# Open_Reactor_Control_System_-_Power_Supp.net
KiCad netlist of a schematic drawn in Altium Designer
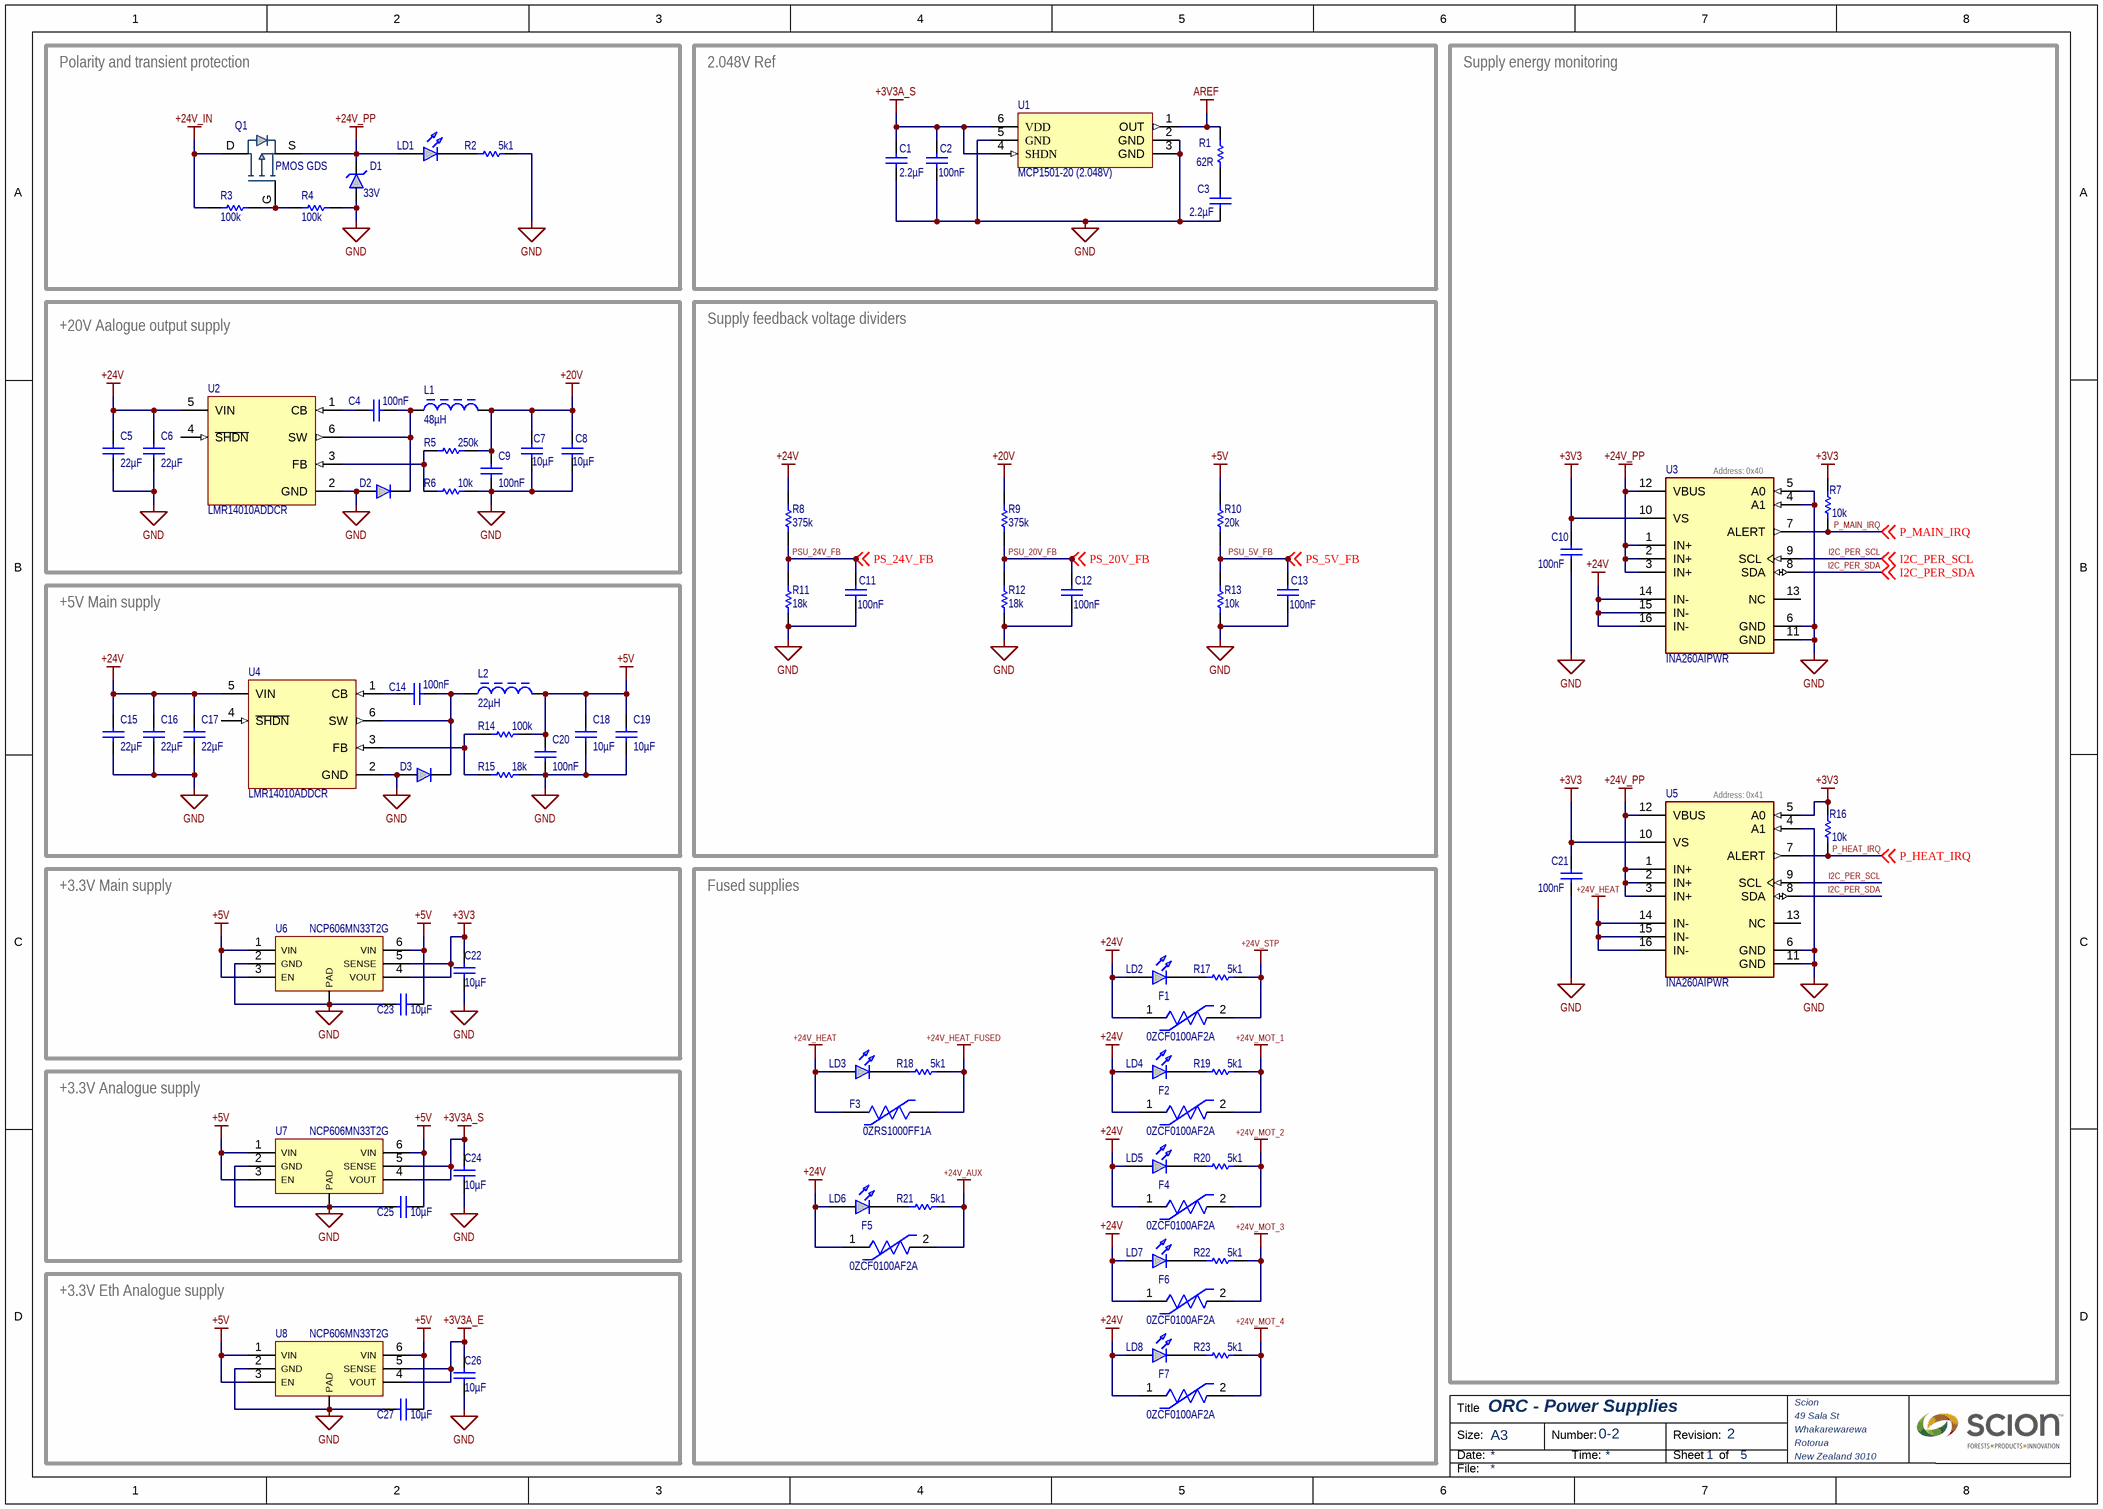
[diagram p0: Open Reactor Control System - Power Supplies.SchDoc]

(export (version "E")
  (design (tool "Eeschema 10.0.6"))
  (components
    (comp (ref "C1")
      (value "2.2µF")
      (footprint "0603_CAP")
      (description "SMD Capacitor")
      (fields (field (name "Comment") "Capacitor"))
      (libsource (lib "Scion Research") (part "CMP-019-00005-2"))
    )
    (comp (ref "C2")
      (value "100nF")
      (footprint "0603_CAP")
      (description "SMD Capacitor")
      (fields (field (name "Comment") "Capacitor"))
      (libsource (lib "Scion Research") (part "CMP-019-00005-2"))
    )
    (comp (ref "C3")
      (value "2.2µF")
      (footprint "0603_CAP")
      (description "SMD Capacitor")
      (fields (field (name "Comment") "Capacitor"))
      (libsource (lib "Scion Research") (part "CMP-019-00005-2"))
    )
    (comp (ref "C4")
      (value "100nF")
      (footprint "0603_CAP")
      (description "SMD Capacitor")
      (fields (field (name "Comment") "Capacitor"))
      (libsource (lib "Scion Research") (part "CMP-019-00005-2"))
    )
    (comp (ref "C5")
      (value "22µF")
      (footprint "1206_CAP")
      (description "SMD Capacitor")
      (fields (field (name "Comment") "Capacitor"))
      (libsource (lib "Scion Research") (part "CMP-019-00005-2"))
    )
    (comp (ref "C6")
      (value "22µF")
      (footprint "1206_CAP")
      (description "SMD Capacitor")
      (fields (field (name "Comment") "Capacitor"))
      (libsource (lib "Scion Research") (part "CMP-019-00005-2"))
    )
    (comp (ref "C7")
      (value "10µF")
      (footprint "1206_CAP")
      (description "SMD Capacitor")
      (fields (field (name "Comment") "Capacitor"))
      (libsource (lib "Scion Research") (part "CMP-019-00005-2"))
    )
    (comp (ref "C8")
      (value "10µF")
      (footprint "1206_CAP")
      (description "SMD Capacitor")
      (fields (field (name "Comment") "Capacitor"))
      (libsource (lib "Scion Research") (part "CMP-019-00005-2"))
    )
    (comp (ref "C9")
      (value "100nF")
      (footprint "0603_CAP")
      (description "SMD Capacitor")
      (fields (field (name "Comment") "Capacitor"))
      (libsource (lib "Scion Research") (part "CMP-019-00005-2"))
    )
    (comp (ref "C10")
      (value "100nF")
      (footprint "0603_CAP")
      (description "SMD Capacitor")
      (fields (field (name "Comment") "Capacitor"))
      (libsource (lib "Scion Research") (part "CMP-019-00005-2"))
    )
    (comp (ref "C11")
      (value "100nF")
      (footprint "0603_CAP")
      (description "SMD Capacitor")
      (fields (field (name "Comment") "Capacitor"))
      (libsource (lib "Scion Research") (part "CMP-019-00005-2"))
    )
    (comp (ref "C12")
      (value "100nF")
      (footprint "0603_CAP")
      (description "SMD Capacitor")
      (fields (field (name "Comment") "Capacitor"))
      (libsource (lib "Scion Research") (part "CMP-019-00005-2"))
    )
    (comp (ref "C13")
      (value "100nF")
      (footprint "0603_CAP")
      (description "SMD Capacitor")
      (fields (field (name "Comment") "Capacitor"))
      (libsource (lib "Scion Research") (part "CMP-019-00005-2"))
    )
    (comp (ref "C14")
      (value "100nF")
      (footprint "0603_CAP")
      (description "SMD Capacitor")
      (fields (field (name "Comment") "Capacitor"))
      (libsource (lib "Scion Research") (part "CMP-019-00005-2"))
    )
    (comp (ref "C15")
      (value "22µF")
      (footprint "1206_CAP")
      (description "SMD Capacitor")
      (fields (field (name "Comment") "Capacitor"))
      (libsource (lib "Scion Research") (part "CMP-019-00005-2"))
    )
    (comp (ref "C16")
      (value "22µF")
      (footprint "1206_CAP")
      (description "SMD Capacitor")
      (fields (field (name "Comment") "Capacitor"))
      (libsource (lib "Scion Research") (part "CMP-019-00005-2"))
    )
    (comp (ref "C17")
      (value "22µF")
      (footprint "1206_CAP")
      (description "SMD Capacitor")
      (fields (field (name "Comment") "Capacitor"))
      (libsource (lib "Scion Research") (part "CMP-019-00005-2"))
    )
    (comp (ref "C18")
      (value "10µF")
      (footprint "0603_CAP")
      (description "SMD Capacitor")
      (fields (field (name "Comment") "Capacitor"))
      (libsource (lib "Scion Research") (part "CMP-019-00005-2"))
    )
    (comp (ref "C19")
      (value "10µF")
      (footprint "0603_CAP")
      (description "SMD Capacitor")
      (fields (field (name "Comment") "Capacitor"))
      (libsource (lib "Scion Research") (part "CMP-019-00005-2"))
    )
    (comp (ref "C20")
      (value "100nF")
      (footprint "0603_CAP")
      (description "SMD Capacitor")
      (fields (field (name "Comment") "Capacitor"))
      (libsource (lib "Scion Research") (part "CMP-019-00005-2"))
    )
    (comp (ref "C21")
      (value "100nF")
      (footprint "0603_CAP")
      (description "SMD Capacitor")
      (fields (field (name "Comment") "Capacitor"))
      (libsource (lib "Scion Research") (part "CMP-019-00005-2"))
    )
    (comp (ref "C22")
      (value "10µF")
      (footprint "0603_CAP")
      (description "SMD Capacitor")
      (fields (field (name "Comment") "Capacitor"))
      (libsource (lib "Scion Research") (part "CMP-019-00005-2"))
    )
    (comp (ref "C23")
      (value "10µF")
      (footprint "0603_CAP")
      (description "SMD Capacitor")
      (fields (field (name "Comment") "Capacitor"))
      (libsource (lib "Scion Research") (part "CMP-019-00005-2"))
    )
    (comp (ref "C24")
      (value "10µF")
      (footprint "0603_CAP")
      (description "SMD Capacitor")
      (fields (field (name "Comment") "Capacitor"))
      (libsource (lib "Scion Research") (part "CMP-019-00005-2"))
    )
    (comp (ref "C25")
      (value "10µF")
      (footprint "0603_CAP")
      (description "SMD Capacitor")
      (fields (field (name "Comment") "Capacitor"))
      (libsource (lib "Scion Research") (part "CMP-019-00005-2"))
    )
    (comp (ref "C26")
      (value "10µF")
      (footprint "0603_CAP")
      (description "SMD Capacitor")
      (fields (field (name "Comment") "Capacitor"))
      (libsource (lib "Scion Research") (part "CMP-019-00005-2"))
    )
    (comp (ref "C27")
      (value "10µF")
      (footprint "0603_CAP")
      (description "SMD Capacitor")
      (fields (field (name "Comment") "Capacitor"))
      (libsource (lib "Scion Research") (part "CMP-019-00005-2"))
    )
    (comp (ref "D1")
      (value "Transil")
      (footprint "SMBJ")
      (description "Transient Voltage Suppressor")
      (fields (field (name "RATED VOLTAGE") "33V"))
      (libsource (lib "Scion Research") (part "CMP-004-0042-1"))
    )
    (comp (ref "D2")
      (value "Diode")
      (footprint "SOD-123")
      (description "SMD Diode")
      (libsource (lib "Scion Research") (part "Diode"))
    )
    (comp (ref "D3")
      (value "Diode")
      (footprint "SOD-123")
      (description "SMD Diode")
      (libsource (lib "Scion Research") (part "Diode"))
    )
    (comp (ref "F1")
      (value "0ZCF0100AF2A")
      (footprint "FP-0ZCF0100AF2A-MFG")
      (description "PTC Resettable Fuse 100A 0.5s 60VDC 0.09 Ohm 2-Pin 2920 T/R")
      (libsource (lib "Scion Research") (part "CMP-00051-1"))
    )
    (comp (ref "F2")
      (value "0ZCF0100AF2A")
      (footprint "FP-0ZCF0100AF2A-MFG")
      (description "PTC Resettable Fuse 100A 0.5s 60VDC 0.09 Ohm 2-Pin 2920 T/R")
      (libsource (lib "Scion Research") (part "CMP-00051-1"))
    )
    (comp (ref "F3")
      (value "0ZRS1000FF1A")
      (footprint "0ZRS1000FF1A-flat")
      (description "PTC Resettable Fuse 10A(hold) 20A(trip) 32VDC 100A 7W 15s 0.006Ohm Radial 23.5 X 4 X 27.9mm Box")
      (libsource (lib "Scion Research") (part "CMP-00049-1"))
    )
    (comp (ref "F4")
      (value "0ZCF0100AF2A")
      (footprint "FP-0ZCF0100AF2A-MFG")
      (description "PTC Resettable Fuse 100A 0.5s 60VDC 0.09 Ohm 2-Pin 2920 T/R")
      (libsource (lib "Scion Research") (part "CMP-00051-1"))
    )
    (comp (ref "F5")
      (value "0ZCF0100AF2A")
      (footprint "FP-0ZCF0100AF2A-MFG")
      (description "PTC Resettable Fuse 100A 0.5s 60VDC 0.09 Ohm 2-Pin 2920 T/R")
      (libsource (lib "Scion Research") (part "CMP-00051-1"))
    )
    (comp (ref "F6")
      (value "0ZCF0100AF2A")
      (footprint "FP-0ZCF0100AF2A-MFG")
      (description "PTC Resettable Fuse 100A 0.5s 60VDC 0.09 Ohm 2-Pin 2920 T/R")
      (libsource (lib "Scion Research") (part "CMP-00051-1"))
    )
    (comp (ref "F7")
      (value "0ZCF0100AF2A")
      (footprint "FP-0ZCF0100AF2A-MFG")
      (description "PTC Resettable Fuse 100A 0.5s 60VDC 0.09 Ohm 2-Pin 2920 T/R")
      (libsource (lib "Scion Research") (part "CMP-00051-1"))
    )
    (comp (ref "L1")
      (value "48µH")
      (footprint "SRR1206")
      (description "Power Inductor")
      (fields (field (name "Comment") "Inductor"))
      (libsource (lib "Scion Research") (part "Inductor"))
    )
    (comp (ref "L2")
      (value "22µH")
      (footprint "BOUR-SRN8040_V")
      (description "Power Inductor")
      (fields (field (name "Comment") "Inductor"))
      (libsource (lib "Scion Research") (part "Inductor"))
    )
    (comp (ref "LD1")
      (value "LED")
      (footprint "0805")
      (description "SMD LED")
      (libsource (lib "Scion Research") (part "CMP-004-00032-1"))
    )
    (comp (ref "LD2")
      (value "LED")
      (footprint "0805")
      (description "SMD LED")
      (libsource (lib "Scion Research") (part "CMP-004-00032-1"))
    )
    (comp (ref "LD3")
      (value "LED")
      (footprint "0805")
      (description "SMD LED")
      (libsource (lib "Scion Research") (part "CMP-004-00032-1"))
    )
    (comp (ref "LD4")
      (value "LED")
      (footprint "0805")
      (description "SMD LED")
      (libsource (lib "Scion Research") (part "CMP-004-00032-1"))
    )
    (comp (ref "LD5")
      (value "LED")
      (footprint "0805")
      (description "SMD LED")
      (libsource (lib "Scion Research") (part "CMP-004-00032-1"))
    )
    (comp (ref "LD6")
      (value "LED")
      (footprint "0805")
      (description "SMD LED")
      (libsource (lib "Scion Research") (part "CMP-004-00032-1"))
    )
    (comp (ref "LD7")
      (value "LED")
      (footprint "0805")
      (description "SMD LED")
      (libsource (lib "Scion Research") (part "CMP-004-00032-1"))
    )
    (comp (ref "LD8")
      (value "LED")
      (footprint "0805")
      (description "SMD LED")
      (libsource (lib "Scion Research") (part "CMP-004-00032-1"))
    )
    (comp (ref "Q1")
      (value "PMOS GDS")
      (footprint "PowerDI 5060-8")
      (description "P Channel MOSFET")
      (libsource (lib "Scion Research") (part "CMP-004-0035-2"))
    )
    (comp (ref "R1")
      (value "Resistor")
      (footprint "0603_RES")
      (description "SMD Resistor")
      (fields (field (name "ALTIUM_VALUE") "62R"))
      (libsource (lib "Scion Research") (part "CMP-009-00177-2"))
    )
    (comp (ref "R2")
      (value "Resistor")
      (footprint "0603_RES")
      (description "SMD Resistor")
      (fields (field (name "ALTIUM_VALUE") "5k1"))
      (libsource (lib "Scion Research") (part "CMP-009-00177-2"))
    )
    (comp (ref "R3")
      (value "Resistor")
      (footprint "0603_RES")
      (description "SMD Resistor")
      (fields (field (name "ALTIUM_VALUE") "100k"))
      (libsource (lib "Scion Research") (part "CMP-009-00177-2"))
    )
    (comp (ref "R4")
      (value "Resistor")
      (footprint "0603_RES")
      (description "SMD Resistor")
      (fields (field (name "ALTIUM_VALUE") "100k"))
      (libsource (lib "Scion Research") (part "CMP-009-00177-2"))
    )
    (comp (ref "R5")
      (value "Resistor")
      (footprint "0603_RES")
      (description "SMD Resistor")
      (fields (field (name "ALTIUM_VALUE") "250k"))
      (libsource (lib "Scion Research") (part "CMP-009-00177-2"))
    )
    (comp (ref "R6")
      (value "Resistor")
      (footprint "0603_RES")
      (description "SMD Resistor")
      (fields (field (name "ALTIUM_VALUE") "10k"))
      (libsource (lib "Scion Research") (part "CMP-009-00177-2"))
    )
    (comp (ref "R7")
      (value "Resistor")
      (footprint "0603_RES")
      (description "SMD Resistor")
      (fields (field (name "ALTIUM_VALUE") "10k"))
      (libsource (lib "Scion Research") (part "CMP-009-00177-2"))
    )
    (comp (ref "R8")
      (value "Resistor")
      (footprint "0603_RES")
      (description "SMD Resistor")
      (fields (field (name "ALTIUM_VALUE") "375k"))
      (libsource (lib "Scion Research") (part "CMP-009-00177-2"))
    )
    (comp (ref "R9")
      (value "Resistor")
      (footprint "0603_RES")
      (description "SMD Resistor")
      (fields (field (name "ALTIUM_VALUE") "375k"))
      (libsource (lib "Scion Research") (part "CMP-009-00177-2"))
    )
    (comp (ref "R10")
      (value "Resistor")
      (footprint "0603_RES")
      (description "SMD Resistor")
      (fields (field (name "ALTIUM_VALUE") "20k"))
      (libsource (lib "Scion Research") (part "CMP-009-00177-2"))
    )
    (comp (ref "R11")
      (value "Resistor")
      (footprint "0603_RES")
      (description "SMD Resistor")
      (fields (field (name "ALTIUM_VALUE") "18k"))
      (libsource (lib "Scion Research") (part "CMP-009-00177-2"))
    )
    (comp (ref "R12")
      (value "Resistor")
      (footprint "0603_RES")
      (description "SMD Resistor")
      (fields (field (name "ALTIUM_VALUE") "18k"))
      (libsource (lib "Scion Research") (part "CMP-009-00177-2"))
    )
    (comp (ref "R13")
      (value "Resistor")
      (footprint "0603_RES")
      (description "SMD Resistor")
      (fields (field (name "ALTIUM_VALUE") "10k"))
      (libsource (lib "Scion Research") (part "CMP-009-00177-2"))
    )
    (comp (ref "R14")
      (value "Resistor")
      (footprint "0603_RES")
      (description "SMD Resistor")
      (fields (field (name "ALTIUM_VALUE") "100k"))
      (libsource (lib "Scion Research") (part "CMP-009-00177-2"))
    )
    (comp (ref "R15")
      (value "Resistor")
      (footprint "0603_RES")
      (description "SMD Resistor")
      (fields (field (name "ALTIUM_VALUE") "18k"))
      (libsource (lib "Scion Research") (part "CMP-009-00177-2"))
    )
    (comp (ref "R16")
      (value "Resistor")
      (footprint "0603_RES")
      (description "SMD Resistor")
      (fields (field (name "ALTIUM_VALUE") "10k"))
      (libsource (lib "Scion Research") (part "CMP-009-00177-2"))
    )
    (comp (ref "R17")
      (value "Resistor")
      (footprint "0603_RES")
      (description "SMD Resistor")
      (fields (field (name "ALTIUM_VALUE") "5k1"))
      (libsource (lib "Scion Research") (part "CMP-009-00177-2"))
    )
    (comp (ref "R18")
      (value "Resistor")
      (footprint "0603_RES")
      (description "SMD Resistor")
      (fields (field (name "ALTIUM_VALUE") "5k1"))
      (libsource (lib "Scion Research") (part "CMP-009-00177-2"))
    )
    (comp (ref "R19")
      (value "Resistor")
      (footprint "0603_RES")
      (description "SMD Resistor")
      (fields (field (name "ALTIUM_VALUE") "5k1"))
      (libsource (lib "Scion Research") (part "CMP-009-00177-2"))
    )
    (comp (ref "R20")
      (value "Resistor")
      (footprint "0603_RES")
      (description "SMD Resistor")
      (fields (field (name "ALTIUM_VALUE") "5k1"))
      (libsource (lib "Scion Research") (part "CMP-009-00177-2"))
    )
    (comp (ref "R21")
      (value "Resistor")
      (footprint "0603_RES")
      (description "SMD Resistor")
      (fields (field (name "ALTIUM_VALUE") "5k1"))
      (libsource (lib "Scion Research") (part "CMP-009-00177-2"))
    )
    (comp (ref "R22")
      (value "Resistor")
      (footprint "0603_RES")
      (description "SMD Resistor")
      (fields (field (name "ALTIUM_VALUE") "5k1"))
      (libsource (lib "Scion Research") (part "CMP-009-00177-2"))
    )
    (comp (ref "R23")
      (value "Resistor")
      (footprint "0603_RES")
      (description "SMD Resistor")
      (fields (field (name "ALTIUM_VALUE") "5k1"))
      (libsource (lib "Scion Research") (part "CMP-009-00177-2"))
    )
    (comp (ref "U1")
      (value "MCP1501-20 (2.048V)")
      (footprint "SOT-6")
      (description "Voltage Reference")
      (libsource (lib "Scion Research") (part "CMP-004-0020-1"))
    )
    (comp (ref "U2")
      (value "LMR14010ADDCR")
      (footprint "FP-DDC0006A-IPC_A")
      (description "7-40VDC-DC buck converter")
      (libsource (lib "Scion Research") (part "LMR14010"))
    )
    (comp (ref "U3")
      (value "INA260AIPWR")
      (footprint "FP-PW0016A-IPC_B")
      (description "Operational Amplifier, 1 Func, 7500uV Offset-Max, PDSO16")
      (libsource (lib "Scion Research") (part "fcceeca0fd405d0f0207f40a7ff7922"))
    )
    (comp (ref "U4")
      (value "LMR14010ADDCR")
      (footprint "FP-DDC0006A-IPC_A")
      (description "7-40VDC-DC buck converter")
      (libsource (lib "Scion Research") (part "LMR14010"))
    )
    (comp (ref "U5")
      (value "INA260AIPWR")
      (footprint "FP-PW0016A-IPC_B")
      (description "Operational Amplifier, 1 Func, 7500uV Offset-Max, PDSO16")
      (libsource (lib "Scion Research") (part "fcceeca0fd405d0f0207f40a7ff7922"))
    )
    (comp (ref "U6")
      (value "NCP606MN33T2G")
      (footprint "QFN95P330X295X100_HS-7N")
      (description "Fixed Positive LDO Regulator, 3.3V, 0.22V Dropout, CMOS")
      (libsource (lib "Scion Research") (part "NCP606MN33T2G-Symbol-1"))
    )
    (comp (ref "U7")
      (value "NCP606MN33T2G")
      (footprint "QFN95P330X295X100_HS-7N")
      (description "Fixed Positive LDO Regulator, 3.3V, 0.22V Dropout, CMOS")
      (libsource (lib "Scion Research") (part "NCP606MN33T2G-Symbol-1"))
    )
    (comp (ref "U8")
      (value "NCP606MN33T2G")
      (footprint "QFN95P330X295X100_HS-7N")
      (description "Fixed Positive LDO Regulator, 3.3V, 0.22V Dropout, CMOS")
      (libsource (lib "Scion Research") (part "NCP606MN33T2G-Symbol-1"))
    )
  )
  (nets
    (net (code "1") (name "+3V3") (class "Default")
      (node (ref "C10") (pin "1") (pinfunction "1_1") (pintype "passive"))
      (node (ref "C21") (pin "1") (pinfunction "1_1") (pintype "passive"))
      (node (ref "C22") (pin "1") (pinfunction "1_1") (pintype "passive"))
      (node (ref "R16") (pin "1") (pinfunction "1_1") (pintype "passive"))
      (node (ref "R7") (pin "1") (pinfunction "1_1") (pintype "passive"))
      (node (ref "U3") (pin "10") (pinfunction "VS_10") (pintype "passive"))
      (node (ref "U5") (pin "10") (pinfunction "VS_10") (pintype "passive"))
      (node (ref "U5") (pin "5") (pinfunction "A0_5") (pintype "input"))
      (node (ref "U6") (pin "4") (pinfunction "VOUT_4") (pintype "passive"))
      (node (ref "U6") (pin "5") (pinfunction "SENSE_5") (pintype "passive"))
    )
    (net (code "2") (name "+3V3A_E") (class "Default")
      (node (ref "C26") (pin "1") (pinfunction "1_1") (pintype "passive"))
      (node (ref "U8") (pin "4") (pinfunction "VOUT_4") (pintype "passive"))
      (node (ref "U8") (pin "5") (pinfunction "SENSE_5") (pintype "passive"))
    )
    (net (code "3") (name "+3V3A_S") (class "Default")
      (node (ref "C1") (pin "1") (pinfunction "1_1") (pintype "passive"))
      (node (ref "C2") (pin "1") (pinfunction "1_1") (pintype "passive"))
      (node (ref "C24") (pin "1") (pinfunction "1_1") (pintype "passive"))
      (node (ref "U1") (pin "4") (pinfunction "SHDN_4") (pintype "input"))
      (node (ref "U1") (pin "6") (pinfunction "VDD_6") (pintype "power_in"))
      (node (ref "U7") (pin "4") (pinfunction "VOUT_4") (pintype "passive"))
      (node (ref "U7") (pin "5") (pinfunction "SENSE_5") (pintype "passive"))
    )
    (net (code "4") (name "+5V") (class "Default")
      (node (ref "C18") (pin "1") (pinfunction "1_1") (pintype "passive"))
      (node (ref "C19") (pin "1") (pinfunction "1_1") (pintype "passive"))
      (node (ref "C20") (pin "1") (pinfunction "1_1") (pintype "passive"))
      (node (ref "C23") (pin "1") (pinfunction "1_1") (pintype "passive"))
      (node (ref "C25") (pin "1") (pinfunction "1_1") (pintype "passive"))
      (node (ref "C27") (pin "1") (pinfunction "1_1") (pintype "passive"))
      (node (ref "L2") (pin "2") (pinfunction "2_2") (pintype "passive"))
      (node (ref "R10") (pin "1") (pinfunction "1_1") (pintype "passive"))
      (node (ref "R14") (pin "2") (pinfunction "2_2") (pintype "passive"))
      (node (ref "U6") (pin "1") (pinfunction "VIN_1") (pintype "passive"))
      (node (ref "U6") (pin "3") (pinfunction "EN_3") (pintype "passive"))
      (node (ref "U6") (pin "6") (pinfunction "VIN_6") (pintype "passive"))
      (node (ref "U7") (pin "1") (pinfunction "VIN_1") (pintype "passive"))
      (node (ref "U7") (pin "3") (pinfunction "EN_3") (pintype "passive"))
      (node (ref "U7") (pin "6") (pinfunction "VIN_6") (pintype "passive"))
      (node (ref "U8") (pin "1") (pinfunction "VIN_1") (pintype "passive"))
      (node (ref "U8") (pin "3") (pinfunction "EN_3") (pintype "passive"))
      (node (ref "U8") (pin "6") (pinfunction "VIN_6") (pintype "passive"))
    )
    (net (code "5") (name "+20V") (class "Default")
      (node (ref "C7") (pin "1") (pinfunction "1_1") (pintype "passive"))
      (node (ref "C8") (pin "1") (pinfunction "1_1") (pintype "passive"))
      (node (ref "C9") (pin "1") (pinfunction "1_1") (pintype "passive"))
      (node (ref "L1") (pin "2") (pinfunction "2_2") (pintype "passive"))
      (node (ref "R5") (pin "2") (pinfunction "2_2") (pintype "passive"))
      (node (ref "R9") (pin "1") (pinfunction "1_1") (pintype "passive"))
    )
    (net (code "6") (name "+24V") (class "Default")
      (node (ref "C15") (pin "1") (pinfunction "1_1") (pintype "passive"))
      (node (ref "C16") (pin "1") (pinfunction "1_1") (pintype "passive"))
      (node (ref "C17") (pin "1") (pinfunction "1_1") (pintype "passive"))
      (node (ref "C5") (pin "1") (pinfunction "1_1") (pintype "passive"))
      (node (ref "C6") (pin "1") (pinfunction "1_1") (pintype "passive"))
      (node (ref "F1") (pin "1") (pinfunction "1_1") (pintype "passive"))
      (node (ref "F2") (pin "1") (pinfunction "1_1") (pintype "passive"))
      (node (ref "F4") (pin "1") (pinfunction "1_1") (pintype "passive"))
      (node (ref "F5") (pin "1") (pinfunction "1_1") (pintype "passive"))
      (node (ref "F6") (pin "1") (pinfunction "1_1") (pintype "passive"))
      (node (ref "F7") (pin "1") (pinfunction "1_1") (pintype "passive"))
      (node (ref "LD2") (pin "2") (pinfunction "A_2") (pintype "passive"))
      (node (ref "LD4") (pin "2") (pinfunction "A_2") (pintype "passive"))
      (node (ref "LD5") (pin "2") (pinfunction "A_2") (pintype "passive"))
      (node (ref "LD6") (pin "2") (pinfunction "A_2") (pintype "passive"))
      (node (ref "LD7") (pin "2") (pinfunction "A_2") (pintype "passive"))
      (node (ref "LD8") (pin "2") (pinfunction "A_2") (pintype "passive"))
      (node (ref "R8") (pin "1") (pinfunction "1_1") (pintype "passive"))
      (node (ref "U2") (pin "5") (pinfunction "VIN_5") (pintype "power_in"))
      (node (ref "U3") (pin "14") (pinfunction "IN-_14") (pintype "passive"))
      (node (ref "U3") (pin "15") (pinfunction "IN-_15") (pintype "passive"))
      (node (ref "U3") (pin "16") (pinfunction "IN-_16") (pintype "passive"))
      (node (ref "U4") (pin "5") (pinfunction "VIN_5") (pintype "power_in"))
    )
    (net (code "7") (name "+24V_AUX") (class "Default")
      (node (ref "F5") (pin "2") (pinfunction "2_2") (pintype "passive"))
      (node (ref "R21") (pin "2") (pinfunction "2_2") (pintype "passive"))
    )
    (net (code "8") (name "+24V_HEAT") (class "Default")
      (node (ref "F3") (pin "1") (pinfunction "1_1") (pintype "passive"))
      (node (ref "LD3") (pin "2") (pinfunction "A_2") (pintype "passive"))
      (node (ref "U5") (pin "14") (pinfunction "IN-_14") (pintype "passive"))
      (node (ref "U5") (pin "15") (pinfunction "IN-_15") (pintype "passive"))
      (node (ref "U5") (pin "16") (pinfunction "IN-_16") (pintype "passive"))
    )
    (net (code "9") (name "+24V_HEAT_FUSED") (class "Default")
      (node (ref "F3") (pin "2") (pinfunction "2_2") (pintype "passive"))
      (node (ref "R18") (pin "2") (pinfunction "2_2") (pintype "passive"))
    )
    (net (code "10") (name "+24V_IN") (class "Default")
      (node (ref "Q1") (pin "D") (pinfunction "D_D") (pintype "passive"))
      (node (ref "R3") (pin "1") (pinfunction "1_1") (pintype "passive"))
    )
    (net (code "11") (name "+24V_MOT_1") (class "Default")
      (node (ref "F2") (pin "2") (pinfunction "2_2") (pintype "passive"))
      (node (ref "R19") (pin "2") (pinfunction "2_2") (pintype "passive"))
    )
    (net (code "12") (name "+24V_MOT_2") (class "Default")
      (node (ref "F4") (pin "2") (pinfunction "2_2") (pintype "passive"))
      (node (ref "R20") (pin "2") (pinfunction "2_2") (pintype "passive"))
    )
    (net (code "13") (name "+24V_MOT_3") (class "Default")
      (node (ref "F6") (pin "2") (pinfunction "2_2") (pintype "passive"))
      (node (ref "R22") (pin "2") (pinfunction "2_2") (pintype "passive"))
    )
    (net (code "14") (name "+24V_MOT_4") (class "Default")
      (node (ref "F7") (pin "2") (pinfunction "2_2") (pintype "passive"))
      (node (ref "R23") (pin "2") (pinfunction "2_2") (pintype "passive"))
    )
    (net (code "15") (name "+24V_PP") (class "Default")
      (node (ref "D1") (pin "2") (pinfunction "K_2") (pintype "passive"))
      (node (ref "LD1") (pin "2") (pinfunction "A_2") (pintype "passive"))
      (node (ref "Q1") (pin "S") (pinfunction "S_S") (pintype "passive"))
      (node (ref "U3") (pin "1") (pinfunction "IN+_1") (pintype "passive"))
      (node (ref "U3") (pin "12") (pinfunction "VBUS_12") (pintype "passive"))
      (node (ref "U3") (pin "2") (pinfunction "IN+_2") (pintype "passive"))
      (node (ref "U3") (pin "3") (pinfunction "IN+_3") (pintype "passive"))
      (node (ref "U5") (pin "1") (pinfunction "IN+_1") (pintype "passive"))
      (node (ref "U5") (pin "12") (pinfunction "VBUS_12") (pintype "passive"))
      (node (ref "U5") (pin "2") (pinfunction "IN+_2") (pintype "passive"))
      (node (ref "U5") (pin "3") (pinfunction "IN+_3") (pintype "passive"))
    )
    (net (code "16") (name "+24V_STP") (class "Default")
      (node (ref "F1") (pin "2") (pinfunction "2_2") (pintype "passive"))
      (node (ref "R17") (pin "2") (pinfunction "2_2") (pintype "passive"))
    )
    (net (code "17") (name "AREF") (class "Default")
      (node (ref "R1") (pin "1") (pinfunction "1_1") (pintype "passive"))
      (node (ref "U1") (pin "1") (pinfunction "OUT_1") (pintype "output"))
    )
    (net (code "18") (name "GND") (class "Default")
      (node (ref "C1") (pin "2") (pinfunction "2_2") (pintype "passive"))
      (node (ref "C10") (pin "2") (pinfunction "2_2") (pintype "passive"))
      (node (ref "C11") (pin "2") (pinfunction "2_2") (pintype "passive"))
      (node (ref "C12") (pin "2") (pinfunction "2_2") (pintype "passive"))
      (node (ref "C13") (pin "2") (pinfunction "2_2") (pintype "passive"))
      (node (ref "C15") (pin "2") (pinfunction "2_2") (pintype "passive"))
      (node (ref "C16") (pin "2") (pinfunction "2_2") (pintype "passive"))
      (node (ref "C17") (pin "2") (pinfunction "2_2") (pintype "passive"))
      (node (ref "C18") (pin "2") (pinfunction "2_2") (pintype "passive"))
      (node (ref "C19") (pin "2") (pinfunction "2_2") (pintype "passive"))
      (node (ref "C2") (pin "2") (pinfunction "2_2") (pintype "passive"))
      (node (ref "C20") (pin "2") (pinfunction "2_2") (pintype "passive"))
      (node (ref "C21") (pin "2") (pinfunction "2_2") (pintype "passive"))
      (node (ref "C22") (pin "2") (pinfunction "2_2") (pintype "passive"))
      (node (ref "C23") (pin "2") (pinfunction "2_2") (pintype "passive"))
      (node (ref "C24") (pin "2") (pinfunction "2_2") (pintype "passive"))
      (node (ref "C25") (pin "2") (pinfunction "2_2") (pintype "passive"))
      (node (ref "C26") (pin "2") (pinfunction "2_2") (pintype "passive"))
      (node (ref "C27") (pin "2") (pinfunction "2_2") (pintype "passive"))
      (node (ref "C3") (pin "1") (pinfunction "1_1") (pintype "passive"))
      (node (ref "C5") (pin "2") (pinfunction "2_2") (pintype "passive"))
      (node (ref "C6") (pin "2") (pinfunction "2_2") (pintype "passive"))
      (node (ref "C7") (pin "2") (pinfunction "2_2") (pintype "passive"))
      (node (ref "C8") (pin "2") (pinfunction "2_2") (pintype "passive"))
      (node (ref "C9") (pin "2") (pinfunction "2_2") (pintype "passive"))
      (node (ref "D1") (pin "1") (pinfunction "A_1") (pintype "passive"))
      (node (ref "D2") (pin "2") (pinfunction "A_2") (pintype "passive"))
      (node (ref "D3") (pin "2") (pinfunction "A_2") (pintype "passive"))
      (node (ref "R11") (pin "1") (pinfunction "1_1") (pintype "passive"))
      (node (ref "R12") (pin "1") (pinfunction "1_1") (pintype "passive"))
      (node (ref "R13") (pin "1") (pinfunction "1_1") (pintype "passive"))
      (node (ref "R15") (pin "2") (pinfunction "2_2") (pintype "passive"))
      (node (ref "R2") (pin "2") (pinfunction "2_2") (pintype "passive"))
      (node (ref "R4") (pin "2") (pinfunction "2_2") (pintype "passive"))
      (node (ref "R6") (pin "2") (pinfunction "2_2") (pintype "passive"))
      (node (ref "U1") (pin "2") (pinfunction "GND_2") (pintype "power_in"))
      (node (ref "U1") (pin "3") (pinfunction "GND_3") (pintype "power_in"))
      (node (ref "U1") (pin "5") (pinfunction "GND_5") (pintype "power_in"))
      (node (ref "U2") (pin "2") (pinfunction "GND_2") (pintype "power_in"))
      (node (ref "U3") (pin "11") (pinfunction "GND_11") (pintype "power_in"))
      (node (ref "U3") (pin "4") (pinfunction "A1_4") (pintype "input"))
      (node (ref "U3") (pin "5") (pinfunction "A0_5") (pintype "input"))
      (node (ref "U3") (pin "6") (pinfunction "GND_6") (pintype "power_in"))
      (node (ref "U4") (pin "2") (pinfunction "GND_2") (pintype "power_in"))
      (node (ref "U5") (pin "11") (pinfunction "GND_11") (pintype "power_in"))
      (node (ref "U5") (pin "4") (pinfunction "A1_4") (pintype "input"))
      (node (ref "U5") (pin "6") (pinfunction "GND_6") (pintype "power_in"))
      (node (ref "U6") (pin "2") (pinfunction "GND_2") (pintype "passive"))
      (node (ref "U6") (pin "PAD") (pinfunction "PAD_PAD") (pintype "passive"))
      (node (ref "U7") (pin "2") (pinfunction "GND_2") (pintype "passive"))
      (node (ref "U7") (pin "PAD") (pinfunction "PAD_PAD") (pintype "passive"))
      (node (ref "U8") (pin "2") (pinfunction "GND_2") (pintype "passive"))
      (node (ref "U8") (pin "PAD") (pinfunction "PAD_PAD") (pintype "passive"))
    )
    (net (code "19") (name "I2C_PER_SCL") (class "Default")
      (node (ref "U3") (pin "9") (pinfunction "SCL_9") (pintype "input"))
      (node (ref "U5") (pin "9") (pinfunction "SCL_9") (pintype "input"))
    )
    (net (code "20") (name "I2C_PER_SDA") (class "Default")
      (node (ref "U3") (pin "8") (pinfunction "SDA_8") (pintype "bidirectional"))
      (node (ref "U5") (pin "8") (pinfunction "SDA_8") (pintype "bidirectional"))
    )
    (net (code "21") (name "Net-(C3-Pad2)") (class "Default")
      (node (ref "C3") (pin "2") (pinfunction "2_2") (pintype "passive"))
      (node (ref "R1") (pin "2") (pinfunction "2_2") (pintype "passive"))
    )
    (net (code "22") (name "Net-(D2-K)") (class "Default")
      (node (ref "C4") (pin "1") (pinfunction "1_1") (pintype "passive"))
      (node (ref "D2") (pin "1") (pinfunction "K_1") (pintype "passive"))
      (node (ref "L1") (pin "1") (pinfunction "1_1") (pintype "passive"))
      (node (ref "U2") (pin "6") (pinfunction "SW_6") (pintype "output"))
    )
    (net (code "23") (name "Net-(D3-K)") (class "Default")
      (node (ref "C14") (pin "1") (pinfunction "1_1") (pintype "passive"))
      (node (ref "D3") (pin "1") (pinfunction "K_1") (pintype "passive"))
      (node (ref "L2") (pin "1") (pinfunction "1_1") (pintype "passive"))
      (node (ref "U4") (pin "6") (pinfunction "SW_6") (pintype "output"))
    )
    (net (code "24") (name "Net-(LD1-K)") (class "Default")
      (node (ref "LD1") (pin "1") (pinfunction "K_1") (pintype "passive"))
      (node (ref "R2") (pin "1") (pinfunction "1_1") (pintype "passive"))
    )
    (net (code "25") (name "Net-(LD2-K)") (class "Default")
      (node (ref "LD2") (pin "1") (pinfunction "K_1") (pintype "passive"))
      (node (ref "R17") (pin "1") (pinfunction "1_1") (pintype "passive"))
    )
    (net (code "26") (name "Net-(LD3-K)") (class "Default")
      (node (ref "LD3") (pin "1") (pinfunction "K_1") (pintype "passive"))
      (node (ref "R18") (pin "1") (pinfunction "1_1") (pintype "passive"))
    )
    (net (code "27") (name "Net-(LD4-K)") (class "Default")
      (node (ref "LD4") (pin "1") (pinfunction "K_1") (pintype "passive"))
      (node (ref "R19") (pin "1") (pinfunction "1_1") (pintype "passive"))
    )
    (net (code "28") (name "Net-(LD5-K)") (class "Default")
      (node (ref "LD5") (pin "1") (pinfunction "K_1") (pintype "passive"))
      (node (ref "R20") (pin "1") (pinfunction "1_1") (pintype "passive"))
    )
    (net (code "29") (name "Net-(LD6-K)") (class "Default")
      (node (ref "LD6") (pin "1") (pinfunction "K_1") (pintype "passive"))
      (node (ref "R21") (pin "1") (pinfunction "1_1") (pintype "passive"))
    )
    (net (code "30") (name "Net-(LD7-K)") (class "Default")
      (node (ref "LD7") (pin "1") (pinfunction "K_1") (pintype "passive"))
      (node (ref "R22") (pin "1") (pinfunction "1_1") (pintype "passive"))
    )
    (net (code "31") (name "Net-(LD8-K)") (class "Default")
      (node (ref "LD8") (pin "1") (pinfunction "K_1") (pintype "passive"))
      (node (ref "R23") (pin "1") (pinfunction "1_1") (pintype "passive"))
    )
    (net (code "32") (name "Net-(Q1-PadG)") (class "Default")
      (node (ref "Q1") (pin "G") (pinfunction "G_G") (pintype "passive"))
      (node (ref "R3") (pin "2") (pinfunction "2_2") (pintype "passive"))
      (node (ref "R4") (pin "1") (pinfunction "1_1") (pintype "passive"))
    )
    (net (code "33") (name "Net-(U2-CB)") (class "Default")
      (node (ref "C4") (pin "2") (pinfunction "2_2") (pintype "passive"))
      (node (ref "U2") (pin "1") (pinfunction "CB_1") (pintype "input"))
    )
    (net (code "34") (name "Net-(U2-FB)") (class "Default")
      (node (ref "R5") (pin "1") (pinfunction "1_1") (pintype "passive"))
      (node (ref "R6") (pin "1") (pinfunction "1_1") (pintype "passive"))
      (node (ref "U2") (pin "3") (pinfunction "FB_3") (pintype "input"))
    )
    (net (code "35") (name "Net-(U4-CB)") (class "Default")
      (node (ref "C14") (pin "2") (pinfunction "2_2") (pintype "passive"))
      (node (ref "U4") (pin "1") (pinfunction "CB_1") (pintype "input"))
    )
    (net (code "36") (name "Net-(U4-FB)") (class "Default")
      (node (ref "R14") (pin "1") (pinfunction "1_1") (pintype "passive"))
      (node (ref "R15") (pin "1") (pinfunction "1_1") (pintype "passive"))
      (node (ref "U4") (pin "3") (pinfunction "FB_3") (pintype "input"))
    )
    (net (code "37") (name "PS_5V_FB") (class "Default")
      (node (ref "C13") (pin "1") (pinfunction "1_1") (pintype "passive"))
      (node (ref "R10") (pin "2") (pinfunction "2_2") (pintype "passive"))
      (node (ref "R13") (pin "2") (pinfunction "2_2") (pintype "passive"))
    )
    (net (code "38") (name "PS_20V_FB") (class "Default")
      (node (ref "C12") (pin "1") (pinfunction "1_1") (pintype "passive"))
      (node (ref "R12") (pin "2") (pinfunction "2_2") (pintype "passive"))
      (node (ref "R9") (pin "2") (pinfunction "2_2") (pintype "passive"))
    )
    (net (code "39") (name "PS_24V_FB") (class "Default")
      (node (ref "C11") (pin "1") (pinfunction "1_1") (pintype "passive"))
      (node (ref "R11") (pin "2") (pinfunction "2_2") (pintype "passive"))
      (node (ref "R8") (pin "2") (pinfunction "2_2") (pintype "passive"))
    )
    (net (code "40") (name "P_HEAT_IRQ") (class "Default")
      (node (ref "R16") (pin "2") (pinfunction "2_2") (pintype "passive"))
      (node (ref "U5") (pin "7") (pinfunction "ALERT_7") (pintype "output"))
    )
    (net (code "41") (name "P_MAIN_IRQ") (class "Default")
      (node (ref "R7") (pin "2") (pinfunction "2_2") (pintype "passive"))
      (node (ref "U3") (pin "7") (pinfunction "ALERT_7") (pintype "output"))
    )
    (net (code "42") (name "unconnected-(U2-~{SHDN}-Pad4)") (class "Default")
      (node (ref "U2") (pin "4") (pinfunction "~{SHDN}_4") (pintype "input"))
    )
    (net (code "43") (name "unconnected-(U3-NC-Pad13)") (class "Default")
      (node (ref "U3") (pin "13") (pinfunction "NC_13") (pintype "passive"))
    )
    (net (code "44") (name "unconnected-(U4-~{SHDN}-Pad4)") (class "Default")
      (node (ref "U4") (pin "4") (pinfunction "~{SHDN}_4") (pintype "input"))
    )
    (net (code "45") (name "unconnected-(U5-NC-Pad13)") (class "Default")
      (node (ref "U5") (pin "13") (pinfunction "NC_13") (pintype "passive"))
    )
  )
)
